# protoCuantumv2.net
KiCad netlist of a schematic drawn in EAGLE
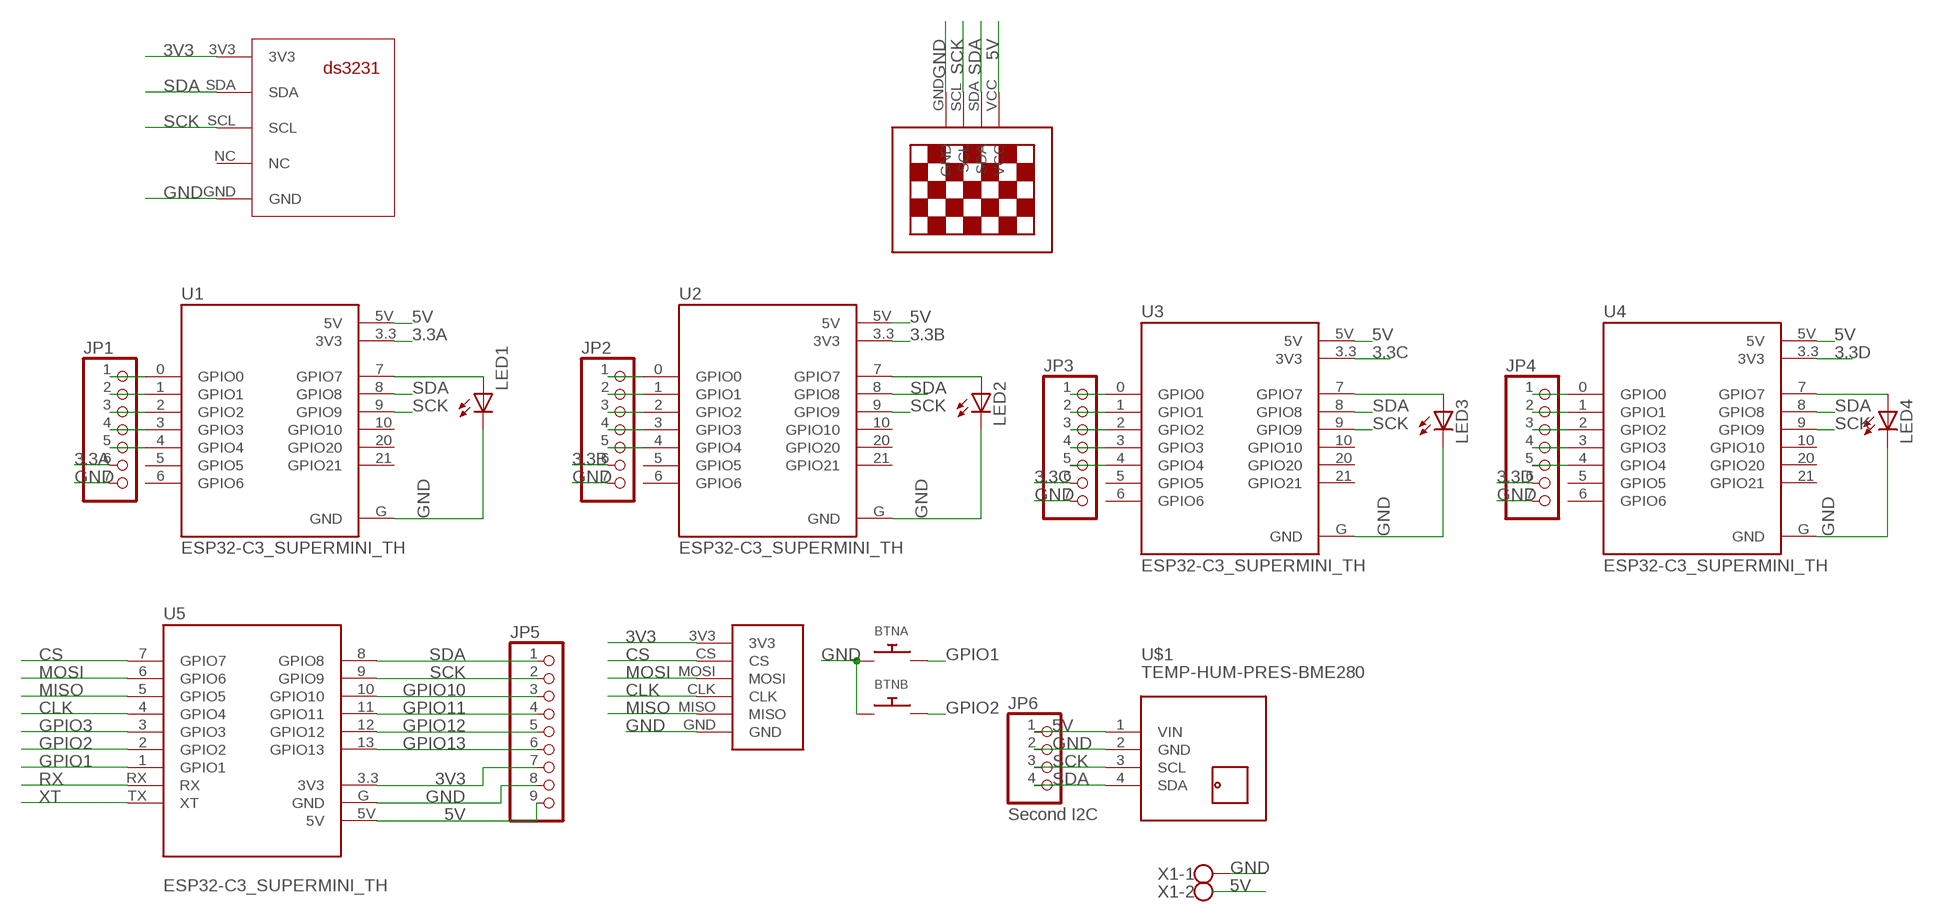
[diagram p0: schematic, sheet 1]

(export (version "E")
  (design (tool "Eeschema 10.0.6"))
  (components
    (comp (ref "BTNA")
      (value "SWITCH_PUSHBUTTONEVQ-PE")
      (footprint "eagle-import:TACT_PANA-EVQ")
      (libsource (lib "eagle-import") (part "SWITCH_PUSHBUTTONEVQ-PE"))
    )
    (comp (ref "BTNB")
      (value "SWITCH_PUSHBUTTONEVQ-PE")
      (footprint "eagle-import:TACT_PANA-EVQ")
      (libsource (lib "eagle-import") (part "SWITCH_PUSHBUTTONEVQ-PE"))
    )
    (comp (ref "JP1")
      (value "PINHD-1X7")
      (footprint "eagle-import:1X07")
      (libsource (lib "eagle-import") (part "PINHD-1X7"))
    )
    (comp (ref "JP2")
      (value "PINHD-1X7")
      (footprint "eagle-import:1X07")
      (libsource (lib "eagle-import") (part "PINHD-1X7"))
    )
    (comp (ref "JP3")
      (value "PINHD-1X7")
      (footprint "eagle-import:1X07")
      (libsource (lib "eagle-import") (part "PINHD-1X7"))
    )
    (comp (ref "JP4")
      (value "PINHD-1X7")
      (footprint "eagle-import:1X07")
      (libsource (lib "eagle-import") (part "PINHD-1X7"))
    )
    (comp (ref "JP5")
      (value "PINHD-1X9")
      (footprint "eagle-import:1X09")
      (libsource (lib "eagle-import") (part "PINHD-1X9"))
    )
    (comp (ref "JP6")
      (value "Second I2C")
      (footprint "eagle-import:1X04")
      (libsource (lib "eagle-import") (part "PINHD-1X4"))
    )
    (comp (ref "LED1")
      (value "LED3MM")
      (footprint "eagle-import:LED3MM")
      (libsource (lib "eagle-import") (part "LED3MM"))
    )
    (comp (ref "LED2")
      (value "LED3MM")
      (footprint "eagle-import:LED3MM")
      (libsource (lib "eagle-import") (part "LED3MM"))
    )
    (comp (ref "LED3")
      (value "LED3MM")
      (footprint "eagle-import:LED3MM")
      (libsource (lib "eagle-import") (part "LED3MM"))
    )
    (comp (ref "LED4")
      (value "LED3MM")
      (footprint "eagle-import:LED3MM")
      (libsource (lib "eagle-import") (part "LED3MM"))
    )
    (comp (ref "U$1")
      (value "TEMP-HUM-PRES-BME280")
      (footprint "eagle-import:TEMP-HUM-PRES-BME280")
      (libsource (lib "eagle-import") (part "TEMP-HUM-PRES-BME280"))
    )
    (comp (ref "U$2")
      (value "SD_KUSKALLA")
      (footprint "eagle-import:SD_KUSKALLA")
      (libsource (lib "eagle-import") (part "SD_KUSKALLA"))
    )
    (comp (ref "U$3")
      (value "13\"OLED13\"OLED")
      (footprint "eagle-import:1.3_OLED")
      (libsource (lib "eagle-import") (part "13{dblquote}OLED13{dblquote}OLED"))
    )
    (comp (ref "U$4")
      (value "RTC")
      (footprint "eagle-import:RTCDS3231FP")
      (libsource (lib "eagle-import") (part "RTC"))
    )
    (comp (ref "U1")
      (value "ESP32-C3_SUPERMINI_TH")
      (footprint "eagle-import:MODULE_ESP32-C3_SUPERMINI_TH")
      (fields (field (name "MF") "Espressif Systems") (field (name "MP") "ESP32-C3 SuperMini_TH"))
      (libsource (lib "eagle-import") (part "ESP32-C3_SUPERMINI_TH"))
    )
    (comp (ref "U2")
      (value "ESP32-C3_SUPERMINI_TH")
      (footprint "eagle-import:MODULE_ESP32-C3_SUPERMINI_TH")
      (fields (field (name "MF") "Espressif Systems") (field (name "MP") "ESP32-C3 SuperMini_TH"))
      (libsource (lib "eagle-import") (part "ESP32-C3_SUPERMINI_TH"))
    )
    (comp (ref "U3")
      (value "ESP32-C3_SUPERMINI_TH")
      (footprint "eagle-import:MODULE_ESP32-C3_SUPERMINI_TH")
      (fields (field (name "MF") "Espressif Systems") (field (name "MP") "ESP32-C3 SuperMini_TH"))
      (libsource (lib "eagle-import") (part "ESP32-C3_SUPERMINI_TH"))
    )
    (comp (ref "U4")
      (value "ESP32-C3_SUPERMINI_TH")
      (footprint "eagle-import:MODULE_ESP32-C3_SUPERMINI_TH")
      (fields (field (name "MF") "Espressif Systems") (field (name "MP") "ESP32-C3 SuperMini_TH"))
      (libsource (lib "eagle-import") (part "ESP32-C3_SUPERMINI_TH"))
    )
    (comp (ref "U5")
      (value "ESP32-C3_SUPERMINI_TH")
      (footprint "eagle-import:MODULE_ESP32-C3_SUPERMINI_TH")
      (fields (field (name "MF") "Espressif Systems") (field (name "MP") "ESP32-S3 SuperMini_TH"))
      (libsource (lib "eagle-import") (part "ESP32-S3_SUPERMINI_TH_ESP32-C3_SUPERMINI_TH"))
    )
    (comp (ref "X1")
      (value "W237-102")
      (footprint "eagle-import:W237-102")
      (fields (field (name "MPN") "237-102"))
      (libsource (lib "eagle-import") (part "W237-102"))
    )
  )
  (nets
    (net (code "1") (name "/3.3A") (class "Default")
      (node (ref "JP1") (pin "6") (pinfunction "6_6") (pintype "passive"))
      (node (ref "U1") (pin "3.3") (pinfunction "3V3_3.3") (pintype "power_in"))
    )
    (net (code "2") (name "/3.3B") (class "Default")
      (node (ref "JP2") (pin "6") (pinfunction "6_6") (pintype "passive"))
      (node (ref "U2") (pin "3.3") (pinfunction "3V3_3.3") (pintype "power_in"))
    )
    (net (code "3") (name "/3.3C") (class "Default")
      (node (ref "JP3") (pin "6") (pinfunction "6_6") (pintype "passive"))
      (node (ref "U3") (pin "3.3") (pinfunction "3V3_3.3") (pintype "power_in"))
    )
    (net (code "4") (name "/3.3D") (class "Default")
      (node (ref "JP4") (pin "6") (pinfunction "6_6") (pintype "passive"))
      (node (ref "U4") (pin "3.3") (pinfunction "3V3_3.3") (pintype "power_in"))
    )
    (net (code "5") (name "/3V3") (class "Default")
      (node (ref "JP5") (pin "7") (pinfunction "7_7") (pintype "passive"))
      (node (ref "U$2") (pin "3V3") (pinfunction "3V3_3V3") (pintype "bidirectional"))
      (node (ref "U$4") (pin "3V3") (pinfunction "3V3_3V3") (pintype "bidirectional"))
      (node (ref "U5") (pin "3.3") (pinfunction "3V3_3.3") (pintype "power_in"))
    )
    (net (code "6") (name "/5V") (class "Default")
      (node (ref "JP5") (pin "9") (pinfunction "9_9") (pintype "passive"))
      (node (ref "JP6") (pin "1") (pinfunction "1_1") (pintype "passive"))
      (node (ref "U$1") (pin "1") (pinfunction "VIN_1") (pintype "power_in"))
      (node (ref "U$3") (pin "VCC") (pinfunction "VCC_VCC") (pintype "bidirectional"))
      (node (ref "U1") (pin "5V") (pinfunction "5V_5V") (pintype "power_in"))
      (node (ref "U2") (pin "5V") (pinfunction "5V_5V") (pintype "power_in"))
      (node (ref "U3") (pin "5V") (pinfunction "5V_5V") (pintype "power_in"))
      (node (ref "U4") (pin "5V") (pinfunction "5V_5V") (pintype "power_in"))
      (node (ref "U5") (pin "5V") (pinfunction "5V_5V") (pintype "power_in"))
      (node (ref "X1") (pin "2") (pinfunction "KL_2") (pintype "passive"))
    )
    (net (code "7") (name "/CLK") (class "Default")
      (node (ref "U$2") (pin "CLK") (pinfunction "CLK_CLK") (pintype "bidirectional"))
      (node (ref "U5") (pin "4") (pinfunction "GPIO4_4") (pintype "bidirectional"))
    )
    (net (code "8") (name "/CS") (class "Default")
      (node (ref "U$2") (pin "CS") (pinfunction "CS_CS") (pintype "bidirectional"))
      (node (ref "U5") (pin "7") (pinfunction "GPIO7_7") (pintype "bidirectional"))
    )
    (net (code "9") (name "/GND") (class "Default")
      (node (ref "BTNA") (pin "P$1") (pinfunction "P$1_P$1") (pintype "passive"))
      (node (ref "BTNB") (pin "P$1") (pinfunction "P$1_P$1") (pintype "passive"))
      (node (ref "JP1") (pin "7") (pinfunction "7_7") (pintype "passive"))
      (node (ref "JP2") (pin "7") (pinfunction "7_7") (pintype "passive"))
      (node (ref "JP3") (pin "7") (pinfunction "7_7") (pintype "passive"))
      (node (ref "JP4") (pin "7") (pinfunction "7_7") (pintype "passive"))
      (node (ref "JP5") (pin "8") (pinfunction "8_8") (pintype "passive"))
      (node (ref "JP6") (pin "2") (pinfunction "2_2") (pintype "passive"))
      (node (ref "LED1") (pin "K") (pinfunction "C_K") (pintype "passive"))
      (node (ref "LED2") (pin "K") (pinfunction "C_K") (pintype "passive"))
      (node (ref "LED3") (pin "K") (pinfunction "C_K") (pintype "passive"))
      (node (ref "LED4") (pin "K") (pinfunction "C_K") (pintype "passive"))
      (node (ref "U$1") (pin "2") (pinfunction "GND_2") (pintype "power_in"))
      (node (ref "U$2") (pin "GND") (pinfunction "GND_GND") (pintype "bidirectional"))
      (node (ref "U$3") (pin "GND") (pinfunction "GND_GND") (pintype "bidirectional"))
      (node (ref "U$4") (pin "GND") (pinfunction "GND_GND") (pintype "bidirectional"))
      (node (ref "U1") (pin "G") (pinfunction "GND_G") (pintype "power_in"))
      (node (ref "U2") (pin "G") (pinfunction "GND_G") (pintype "power_in"))
      (node (ref "U3") (pin "G") (pinfunction "GND_G") (pintype "power_in"))
      (node (ref "U4") (pin "G") (pinfunction "GND_G") (pintype "power_in"))
      (node (ref "U5") (pin "G") (pinfunction "GND_G") (pintype "power_in"))
      (node (ref "X1") (pin "1") (pinfunction "KL_1") (pintype "passive"))
    )
    (net (code "10") (name "/GPIO1") (class "Default")
      (node (ref "BTNA") (pin "P$2") (pinfunction "P$2_P$2") (pintype "passive"))
      (node (ref "U5") (pin "1") (pinfunction "GPIO1_1") (pintype "bidirectional"))
    )
    (net (code "11") (name "/GPIO2") (class "Default")
      (node (ref "BTNB") (pin "P$2") (pinfunction "P$2_P$2") (pintype "passive"))
      (node (ref "U5") (pin "2") (pinfunction "GPIO2_2") (pintype "bidirectional"))
    )
    (net (code "12") (name "/GPIO3") (class "Default")
      (node (ref "U5") (pin "3") (pinfunction "GPIO3_3") (pintype "bidirectional"))
    )
    (net (code "13") (name "/GPIO10") (class "Default")
      (node (ref "JP5") (pin "3") (pinfunction "3_3") (pintype "passive"))
      (node (ref "U5") (pin "10") (pinfunction "GPIO10_10") (pintype "bidirectional"))
    )
    (net (code "14") (name "/GPIO11") (class "Default")
      (node (ref "JP5") (pin "4") (pinfunction "4_4") (pintype "passive"))
      (node (ref "U5") (pin "11") (pinfunction "GPIO11_11") (pintype "bidirectional"))
    )
    (net (code "15") (name "/GPIO12") (class "Default")
      (node (ref "JP5") (pin "5") (pinfunction "5_5") (pintype "passive"))
      (node (ref "U5") (pin "12") (pinfunction "GPIO12_12") (pintype "bidirectional"))
    )
    (net (code "16") (name "/GPIO13") (class "Default")
      (node (ref "JP5") (pin "6") (pinfunction "6_6") (pintype "passive"))
      (node (ref "U5") (pin "13") (pinfunction "GPIO13_13") (pintype "bidirectional"))
    )
    (net (code "17") (name "/MISO") (class "Default")
      (node (ref "U$2") (pin "MISO") (pinfunction "MISO_MISO") (pintype "bidirectional"))
      (node (ref "U5") (pin "5") (pinfunction "GPIO5_5") (pintype "bidirectional"))
    )
    (net (code "18") (name "/MOSI") (class "Default")
      (node (ref "U$2") (pin "MOSI") (pinfunction "MOSI_MOSI") (pintype "bidirectional"))
      (node (ref "U5") (pin "6") (pinfunction "GPIO6_6") (pintype "bidirectional"))
    )
    (net (code "19") (name "/RX") (class "Default")
      (node (ref "U5") (pin "RX") (pinfunction "RX_RX") (pintype "bidirectional"))
    )
    (net (code "20") (name "/SCK") (class "Default")
      (node (ref "JP5") (pin "2") (pinfunction "2_2") (pintype "passive"))
      (node (ref "JP6") (pin "3") (pinfunction "3_3") (pintype "passive"))
      (node (ref "U$1") (pin "3") (pinfunction "SCL_3") (pintype "bidirectional"))
      (node (ref "U$3") (pin "SCL") (pinfunction "SCL_SCL") (pintype "bidirectional"))
      (node (ref "U$4") (pin "SCL") (pinfunction "SCL_SCL") (pintype "bidirectional"))
      (node (ref "U1") (pin "9") (pinfunction "GPIO9_9") (pintype "bidirectional"))
      (node (ref "U2") (pin "9") (pinfunction "GPIO9_9") (pintype "bidirectional"))
      (node (ref "U3") (pin "9") (pinfunction "GPIO9_9") (pintype "bidirectional"))
      (node (ref "U4") (pin "9") (pinfunction "GPIO9_9") (pintype "bidirectional"))
      (node (ref "U5") (pin "9") (pinfunction "GPIO9_9") (pintype "bidirectional"))
    )
    (net (code "21") (name "/SDA") (class "Default")
      (node (ref "JP5") (pin "1") (pinfunction "1_1") (pintype "passive"))
      (node (ref "JP6") (pin "4") (pinfunction "4_4") (pintype "passive"))
      (node (ref "U$1") (pin "4") (pinfunction "SDA_4") (pintype "bidirectional"))
      (node (ref "U$3") (pin "SDA") (pinfunction "SDA_SDA") (pintype "bidirectional"))
      (node (ref "U$4") (pin "SDA") (pinfunction "SDA_SDA") (pintype "bidirectional"))
      (node (ref "U1") (pin "8") (pinfunction "GPIO8_8") (pintype "bidirectional"))
      (node (ref "U2") (pin "8") (pinfunction "GPIO8_8") (pintype "bidirectional"))
      (node (ref "U3") (pin "8") (pinfunction "GPIO8_8") (pintype "bidirectional"))
      (node (ref "U4") (pin "8") (pinfunction "GPIO8_8") (pintype "bidirectional"))
      (node (ref "U5") (pin "8") (pinfunction "GPIO8_8") (pintype "bidirectional"))
    )
    (net (code "22") (name "/XT") (class "Default")
      (node (ref "U5") (pin "TX") (pinfunction "XT_TX") (pintype "bidirectional"))
    )
    (net (code "23") (name "Net-(U1-GPIO0)") (class "Default")
      (node (ref "JP1") (pin "1") (pinfunction "1_1") (pintype "passive"))
      (node (ref "U1") (pin "0") (pinfunction "GPIO0_0") (pintype "bidirectional"))
    )
    (net (code "24") (name "Net-(U1-GPIO1)") (class "Default")
      (node (ref "JP1") (pin "2") (pinfunction "2_2") (pintype "passive"))
      (node (ref "U1") (pin "1") (pinfunction "GPIO1_1") (pintype "bidirectional"))
    )
    (net (code "25") (name "Net-(U1-GPIO2)") (class "Default")
      (node (ref "JP1") (pin "3") (pinfunction "3_3") (pintype "passive"))
      (node (ref "U1") (pin "2") (pinfunction "GPIO2_2") (pintype "bidirectional"))
    )
    (net (code "26") (name "Net-(U1-GPIO3)") (class "Default")
      (node (ref "JP1") (pin "4") (pinfunction "4_4") (pintype "passive"))
      (node (ref "U1") (pin "3") (pinfunction "GPIO3_3") (pintype "bidirectional"))
    )
    (net (code "27") (name "Net-(U1-GPIO4)") (class "Default")
      (node (ref "JP1") (pin "5") (pinfunction "5_5") (pintype "passive"))
      (node (ref "U1") (pin "4") (pinfunction "GPIO4_4") (pintype "bidirectional"))
    )
    (net (code "28") (name "Net-(U1-GPIO7)") (class "Default")
      (node (ref "LED1") (pin "A") (pinfunction "A_A") (pintype "passive"))
      (node (ref "U1") (pin "7") (pinfunction "GPIO7_7") (pintype "bidirectional"))
    )
    (net (code "29") (name "Net-(U2-GPIO0)") (class "Default")
      (node (ref "JP2") (pin "1") (pinfunction "1_1") (pintype "passive"))
      (node (ref "U2") (pin "0") (pinfunction "GPIO0_0") (pintype "bidirectional"))
    )
    (net (code "30") (name "Net-(U2-GPIO1)") (class "Default")
      (node (ref "JP2") (pin "2") (pinfunction "2_2") (pintype "passive"))
      (node (ref "U2") (pin "1") (pinfunction "GPIO1_1") (pintype "bidirectional"))
    )
    (net (code "31") (name "Net-(U2-GPIO2)") (class "Default")
      (node (ref "JP2") (pin "3") (pinfunction "3_3") (pintype "passive"))
      (node (ref "U2") (pin "2") (pinfunction "GPIO2_2") (pintype "bidirectional"))
    )
    (net (code "32") (name "Net-(U2-GPIO3)") (class "Default")
      (node (ref "JP2") (pin "4") (pinfunction "4_4") (pintype "passive"))
      (node (ref "U2") (pin "3") (pinfunction "GPIO3_3") (pintype "bidirectional"))
    )
    (net (code "33") (name "Net-(U2-GPIO4)") (class "Default")
      (node (ref "JP2") (pin "5") (pinfunction "5_5") (pintype "passive"))
      (node (ref "U2") (pin "4") (pinfunction "GPIO4_4") (pintype "bidirectional"))
    )
    (net (code "34") (name "Net-(U2-GPIO7)") (class "Default")
      (node (ref "LED2") (pin "A") (pinfunction "A_A") (pintype "passive"))
      (node (ref "U2") (pin "7") (pinfunction "GPIO7_7") (pintype "bidirectional"))
    )
    (net (code "35") (name "Net-(U3-GPIO0)") (class "Default")
      (node (ref "JP3") (pin "1") (pinfunction "1_1") (pintype "passive"))
      (node (ref "U3") (pin "0") (pinfunction "GPIO0_0") (pintype "bidirectional"))
    )
    (net (code "36") (name "Net-(U3-GPIO1)") (class "Default")
      (node (ref "JP3") (pin "2") (pinfunction "2_2") (pintype "passive"))
      (node (ref "U3") (pin "1") (pinfunction "GPIO1_1") (pintype "bidirectional"))
    )
    (net (code "37") (name "Net-(U3-GPIO2)") (class "Default")
      (node (ref "JP3") (pin "3") (pinfunction "3_3") (pintype "passive"))
      (node (ref "U3") (pin "2") (pinfunction "GPIO2_2") (pintype "bidirectional"))
    )
    (net (code "38") (name "Net-(U3-GPIO3)") (class "Default")
      (node (ref "JP3") (pin "4") (pinfunction "4_4") (pintype "passive"))
      (node (ref "U3") (pin "3") (pinfunction "GPIO3_3") (pintype "bidirectional"))
    )
    (net (code "39") (name "Net-(U3-GPIO4)") (class "Default")
      (node (ref "JP3") (pin "5") (pinfunction "5_5") (pintype "passive"))
      (node (ref "U3") (pin "4") (pinfunction "GPIO4_4") (pintype "bidirectional"))
    )
    (net (code "40") (name "Net-(U3-GPIO7)") (class "Default")
      (node (ref "LED3") (pin "A") (pinfunction "A_A") (pintype "passive"))
      (node (ref "U3") (pin "7") (pinfunction "GPIO7_7") (pintype "bidirectional"))
    )
    (net (code "41") (name "Net-(U4-GPIO0)") (class "Default")
      (node (ref "JP4") (pin "1") (pinfunction "1_1") (pintype "passive"))
      (node (ref "U4") (pin "0") (pinfunction "GPIO0_0") (pintype "bidirectional"))
    )
    (net (code "42") (name "Net-(U4-GPIO1)") (class "Default")
      (node (ref "JP4") (pin "2") (pinfunction "2_2") (pintype "passive"))
      (node (ref "U4") (pin "1") (pinfunction "GPIO1_1") (pintype "bidirectional"))
    )
    (net (code "43") (name "Net-(U4-GPIO2)") (class "Default")
      (node (ref "JP4") (pin "3") (pinfunction "3_3") (pintype "passive"))
      (node (ref "U4") (pin "2") (pinfunction "GPIO2_2") (pintype "bidirectional"))
    )
    (net (code "44") (name "Net-(U4-GPIO3)") (class "Default")
      (node (ref "JP4") (pin "4") (pinfunction "4_4") (pintype "passive"))
      (node (ref "U4") (pin "3") (pinfunction "GPIO3_3") (pintype "bidirectional"))
    )
    (net (code "45") (name "Net-(U4-GPIO4)") (class "Default")
      (node (ref "JP4") (pin "5") (pinfunction "5_5") (pintype "passive"))
      (node (ref "U4") (pin "4") (pinfunction "GPIO4_4") (pintype "bidirectional"))
    )
    (net (code "46") (name "Net-(U4-GPIO7)") (class "Default")
      (node (ref "LED4") (pin "A") (pinfunction "A_A") (pintype "passive"))
      (node (ref "U4") (pin "7") (pinfunction "GPIO7_7") (pintype "bidirectional"))
    )
    (net (code "47") (name "unconnected-(U$4-PadNC)") (class "Default")
      (node (ref "U$4") (pin "NC") (pinfunction "NC_NC") (pintype "bidirectional"))
    )
    (net (code "48") (name "unconnected-(U1-GPIO5-Pad5)") (class "Default")
      (node (ref "U1") (pin "5") (pinfunction "GPIO5_5") (pintype "bidirectional"))
    )
    (net (code "49") (name "unconnected-(U1-GPIO6-Pad6)") (class "Default")
      (node (ref "U1") (pin "6") (pinfunction "GPIO6_6") (pintype "bidirectional"))
    )
    (net (code "50") (name "unconnected-(U1-GPIO10-Pad10)") (class "Default")
      (node (ref "U1") (pin "10") (pinfunction "GPIO10_10") (pintype "bidirectional"))
    )
    (net (code "51") (name "unconnected-(U1-GPIO20-Pad20)") (class "Default")
      (node (ref "U1") (pin "20") (pinfunction "GPIO20_20") (pintype "bidirectional"))
    )
    (net (code "52") (name "unconnected-(U1-GPIO21-Pad21)") (class "Default")
      (node (ref "U1") (pin "21") (pinfunction "GPIO21_21") (pintype "bidirectional"))
    )
    (net (code "53") (name "unconnected-(U2-GPIO5-Pad5)") (class "Default")
      (node (ref "U2") (pin "5") (pinfunction "GPIO5_5") (pintype "bidirectional"))
    )
    (net (code "54") (name "unconnected-(U2-GPIO6-Pad6)") (class "Default")
      (node (ref "U2") (pin "6") (pinfunction "GPIO6_6") (pintype "bidirectional"))
    )
    (net (code "55") (name "unconnected-(U2-GPIO10-Pad10)") (class "Default")
      (node (ref "U2") (pin "10") (pinfunction "GPIO10_10") (pintype "bidirectional"))
    )
    (net (code "56") (name "unconnected-(U2-GPIO20-Pad20)") (class "Default")
      (node (ref "U2") (pin "20") (pinfunction "GPIO20_20") (pintype "bidirectional"))
    )
    (net (code "57") (name "unconnected-(U2-GPIO21-Pad21)") (class "Default")
      (node (ref "U2") (pin "21") (pinfunction "GPIO21_21") (pintype "bidirectional"))
    )
    (net (code "58") (name "unconnected-(U3-GPIO5-Pad5)") (class "Default")
      (node (ref "U3") (pin "5") (pinfunction "GPIO5_5") (pintype "bidirectional"))
    )
    (net (code "59") (name "unconnected-(U3-GPIO6-Pad6)") (class "Default")
      (node (ref "U3") (pin "6") (pinfunction "GPIO6_6") (pintype "bidirectional"))
    )
    (net (code "60") (name "unconnected-(U3-GPIO10-Pad10)") (class "Default")
      (node (ref "U3") (pin "10") (pinfunction "GPIO10_10") (pintype "bidirectional"))
    )
    (net (code "61") (name "unconnected-(U3-GPIO20-Pad20)") (class "Default")
      (node (ref "U3") (pin "20") (pinfunction "GPIO20_20") (pintype "bidirectional"))
    )
    (net (code "62") (name "unconnected-(U3-GPIO21-Pad21)") (class "Default")
      (node (ref "U3") (pin "21") (pinfunction "GPIO21_21") (pintype "bidirectional"))
    )
    (net (code "63") (name "unconnected-(U4-GPIO5-Pad5)") (class "Default")
      (node (ref "U4") (pin "5") (pinfunction "GPIO5_5") (pintype "bidirectional"))
    )
    (net (code "64") (name "unconnected-(U4-GPIO6-Pad6)") (class "Default")
      (node (ref "U4") (pin "6") (pinfunction "GPIO6_6") (pintype "bidirectional"))
    )
    (net (code "65") (name "unconnected-(U4-GPIO10-Pad10)") (class "Default")
      (node (ref "U4") (pin "10") (pinfunction "GPIO10_10") (pintype "bidirectional"))
    )
    (net (code "66") (name "unconnected-(U4-GPIO20-Pad20)") (class "Default")
      (node (ref "U4") (pin "20") (pinfunction "GPIO20_20") (pintype "bidirectional"))
    )
    (net (code "67") (name "unconnected-(U4-GPIO21-Pad21)") (class "Default")
      (node (ref "U4") (pin "21") (pinfunction "GPIO21_21") (pintype "bidirectional"))
    )
  )
)
